# BatteryHullBoard.net
KiCad netlist of a schematic drawn in EAGLE
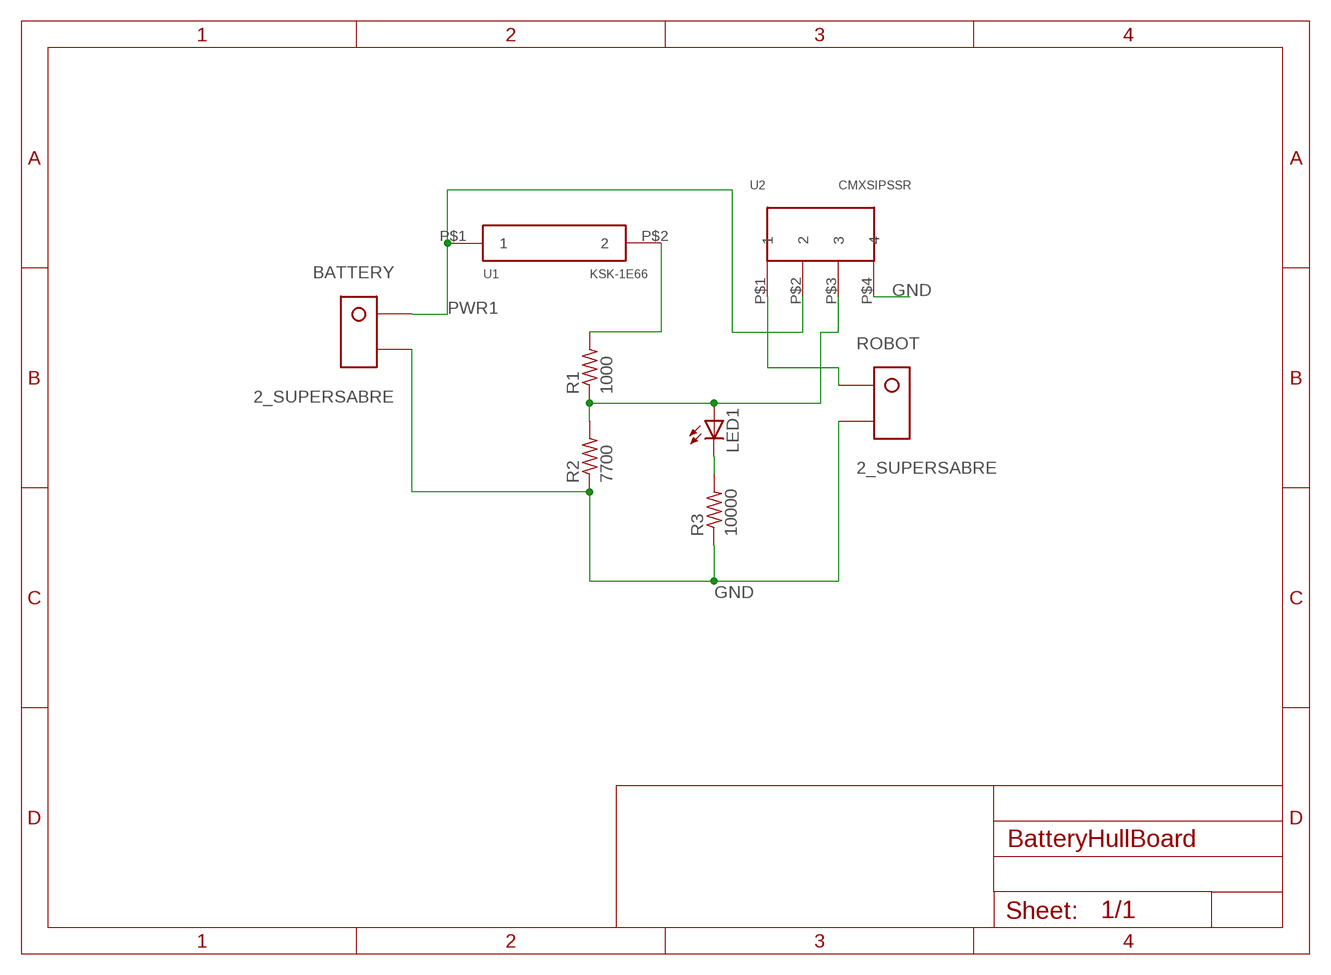
[diagram p0: schematic, sheet 1]

(export (version "E")
  (design (tool "Eeschema 10.0.6"))
  (components
    (comp (ref "BATTERY")
      (value "2_SUPERSABRE")
      (footprint "eagle-import:SUPERSABRE_2CIRCUIT")
      (libsource (lib "eagle-import") (part "2_SUPERSABRE"))
    )
    (comp (ref "LED1")
      (value "LED5MM")
      (footprint "eagle-import:LED5MM")
      (libsource (lib "eagle-import") (part "LED5MM"))
    )
    (comp (ref "R1")
      (value "1000")
      (footprint "eagle-import:R0805")
      (libsource (lib "eagle-import") (part "R-US_R0805"))
    )
    (comp (ref "R2")
      (value "7700")
      (footprint "eagle-import:R0805")
      (libsource (lib "eagle-import") (part "R-US_R0805"))
    )
    (comp (ref "R3")
      (value "10000")
      (footprint "eagle-import:R0805")
      (libsource (lib "eagle-import") (part "R-US_R0805"))
    )
    (comp (ref "ROBOT")
      (value "2_SUPERSABRE")
      (footprint "eagle-import:SUPERSABRE_2CIRCUIT")
      (libsource (lib "eagle-import") (part "2_SUPERSABRE"))
    )
    (comp (ref "U1")
      (value "KSK-1E66")
      (footprint "eagle-import:KSK-1E66")
      (libsource (lib "eagle-import") (part "KSK-1E66"))
    )
    (comp (ref "U2")
      (value "CMXSIPSSR")
      (footprint "eagle-import:CMXSIPSSR")
      (libsource (lib "eagle-import") (part "CMXSIPSSR"))
    )
  )
  (nets
    (net (code "1") (name "/GND") (class "Default")
      (node (ref "BATTERY") (pin "P$2") (pinfunction "P$2_P$2") (pintype "bidirectional"))
      (node (ref "R2") (pin "1") (pinfunction "1_1") (pintype "passive"))
      (node (ref "R3") (pin "1") (pinfunction "1_1") (pintype "passive"))
      (node (ref "ROBOT") (pin "P$2") (pinfunction "P$2_P$2") (pintype "bidirectional"))
      (node (ref "U2") (pin "P$4") (pinfunction "4_P$4") (pintype "bidirectional"))
    )
    (net (code "2") (name "/PWR1") (class "Default")
      (node (ref "BATTERY") (pin "P$1") (pinfunction "P$1_P$1") (pintype "bidirectional"))
      (node (ref "U1") (pin "P$1") (pinfunction "1_P$1") (pintype "input"))
      (node (ref "U2") (pin "P$2") (pinfunction "2_P$2") (pintype "bidirectional"))
    )
    (net (code "3") (name "Net-(LED1-C)") (class "Default")
      (node (ref "LED1") (pin "K") (pinfunction "C_K") (pintype "passive"))
      (node (ref "R3") (pin "2") (pinfunction "2_2") (pintype "passive"))
    )
    (net (code "4") (name "Net-(U1-2)") (class "Default")
      (node (ref "R1") (pin "2") (pinfunction "2_2") (pintype "passive"))
      (node (ref "U1") (pin "P$2") (pinfunction "2_P$2") (pintype "output"))
    )
    (net (code "5") (name "Net-(U2-1)") (class "Default")
      (node (ref "ROBOT") (pin "P$1") (pinfunction "P$1_P$1") (pintype "bidirectional"))
      (node (ref "U2") (pin "P$1") (pinfunction "1_P$1") (pintype "bidirectional"))
    )
    (net (code "6") (name "Net-(U2-3)") (class "Default")
      (node (ref "LED1") (pin "A") (pinfunction "A_A") (pintype "passive"))
      (node (ref "R1") (pin "1") (pinfunction "1_1") (pintype "passive"))
      (node (ref "R2") (pin "2") (pinfunction "2_2") (pintype "passive"))
      (node (ref "U2") (pin "P$3") (pinfunction "3_P$3") (pintype "bidirectional"))
    )
  )
)
